# 2_Battery.net
KiCad netlist of a schematic drawn in Altium Designer
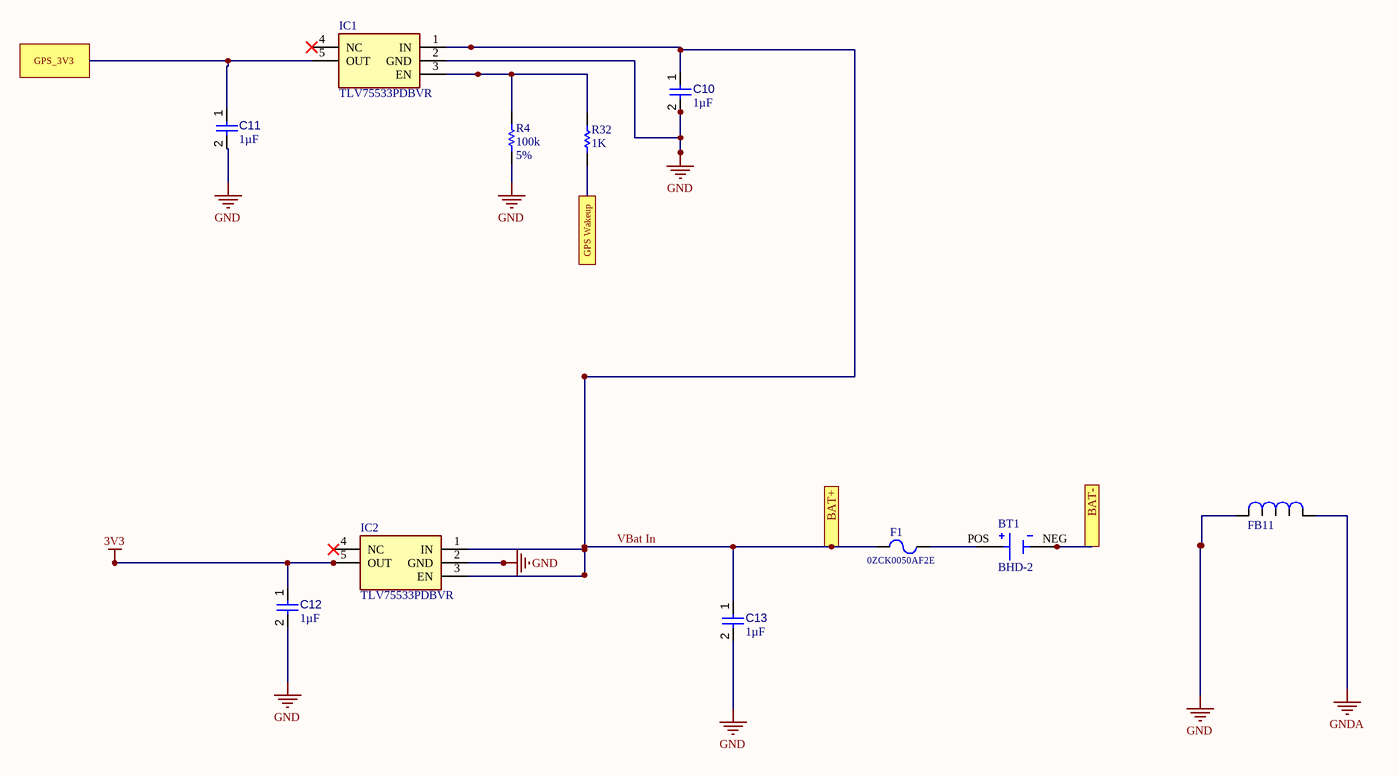
[diagram p0: [2]Battery.SchDoc]

(export (version "E")
  (design (tool "Eeschema 10.0.6"))
  (components
    (comp (ref "BT1")
      (value "BHD-2")
      (footprint "BAT_BHD-2:BAT_BHD-2")
      (description "BATTERY HOLDER D PC PIN")
      (fields
        (field (name "MF") "MPD")
        (field (name "BUYPART") "https://www.snapeda.com/parts/BHD-2/Memory%20Protection%20Devices/view-part/4219639/?ref=eda")
      )
      (libsource (lib "Schlib_For_High_Voltage_Sensor") (part "BHD-2"))
    )
    (comp (ref "C10")
      (value "1µF")
      (footprint "CAPC1608X90X40ML10T20")
      (description "Chip Capacitor, 1 uF, +/- 10%, 25 V, 0603 (1608 Metric)")
      (fields (field (name "TOLERANCE") "10%") (field (name "Comment") "Capacitor 1 uF +/- 10% 25 V 0603"))
      (libsource (lib "Latium Technologies") (part "CAP-NP-2"))
    )
    (comp (ref "C11")
      (value "1µF")
      (footprint "CAPC1608X90X40ML10T20")
      (description "Chip Capacitor, 1 uF, +/- 10%, 25 V, 0603 (1608 Metric)")
      (fields (field (name "TOLERANCE") "10%") (field (name "Comment") "Capacitor 1 uF +/- 10% 25 V 0603"))
      (libsource (lib "Latium Technologies") (part "CAP-NP-2"))
    )
    (comp (ref "C12")
      (value "1µF")
      (footprint "CAPC1608X90X40ML10T20")
      (description "Chip Capacitor, 1 uF, +/- 10%, 25 V, 0603 (1608 Metric)")
      (fields (field (name "TOLERANCE") "10%") (field (name "Comment") "Capacitor 1 uF +/- 10% 25 V 0603"))
      (libsource (lib "Latium Technologies") (part "CAP-NP-2"))
    )
    (comp (ref "C13")
      (value "1µF")
      (footprint "CAPC1608X90X40ML10T20")
      (description "Chip Capacitor, 1 uF, +/- 10%, 25 V, 0603 (1608 Metric)")
      (fields (field (name "TOLERANCE") "10%") (field (name "Comment") "Capacitor 1 uF +/- 10% 25 V 0603"))
      (libsource (lib "Latium Technologies") (part "CAP-NP-2"))
    )
    (comp (ref "F1")
      (value "PTC 9V 500mA")
      (footprint "PcbLibForHigh_Voltage_Sensor:PTC RESET FUSE 9V 500MA 0805")
      (description "PTC RESET FUSE 9V 500MA 0805")
      (fields (field (name "MF PN") "0ZCK0050AF2E"))
      (libsource (lib "MasterLib") (part "PTC RESET FUSE 9V 500MA 0805"))
    )
    (comp (ref "FB11")
      (value "BLM18AG102SN1D")
      (footprint "Ferrite Bead")
      (description "Ferrite Bead 1KOhm @100MHz")
      (libsource (lib "MasterLib") (part "Ferrite Bead"))
    )
    (comp (ref "IC1")
      (value "TLV75533PDBVR")
      (footprint "SamacSys:SOT95P280X145-5N")
      (description "Integrated Circuit")
      (fields (field (name "MOUSER PART NUMBER") "595-TLV75533PDBVR"))
      (libsource (lib "*") (part "TLV75533PDBVR"))
    )
    (comp (ref "IC2")
      (value "TLV75533PDBVR")
      (footprint "SamacSys:SOT95P280X145-5N")
      (description "Integrated Circuit")
      (fields (field (name "MOUSER PART NUMBER") "595-TLV75533PDBVR"))
      (libsource (lib "*") (part "TLV75533PDBVR"))
    )
    (comp (ref "R4")
      (value "100k")
      (footprint "RES 0603")
      (description "RES 100K 5% 0.1W [0603]")
      (fields (field (name "TOLERANCE") "5%"))
      (libsource (lib "MasterLib") (part "RES 3.3M 1% 0.1W [0603]"))
    )
    (comp (ref "R32")
      (value "1K")
      (footprint "RES 0603")
      (description "1K 1% 0.1W [0603]")
      (fields (field (name "TOLERANCE") "1%"))
      (libsource (lib "MasterLib") (part "RES 3.3M 1% 0.1W [0603]"))
    )
  )
  (nets
    (net (code "1") (name "/BAT-") (class "Default")
      (node (ref "BT1") (pin "NEG") (pinfunction "NEG_NEG") (pintype "passive"))
    )
    (net (code "2") (name "/GPS Wakeup") (class "Default")
      (node (ref "R32") (pin "2") (pinfunction "2_2") (pintype "passive"))
    )
    (net (code "3") (name "/GPS_3V3") (class "Default")
      (node (ref "C11") (pin "1") (pinfunction "1_1") (pintype "passive"))
      (node (ref "IC1") (pin "5") (pinfunction "OUT_5") (pintype "passive"))
    )
    (net (code "4") (name "/VBat In") (class "Default")
      (node (ref "C10") (pin "1") (pinfunction "1_1") (pintype "passive"))
      (node (ref "C13") (pin "1") (pinfunction "1_1") (pintype "passive"))
      (node (ref "F1") (pin "1") (pinfunction "1_1") (pintype "passive"))
      (node (ref "IC1") (pin "1") (pinfunction "IN_1") (pintype "passive"))
      (node (ref "IC2") (pin "1") (pinfunction "IN_1") (pintype "passive"))
      (node (ref "IC2") (pin "3") (pinfunction "EN_3") (pintype "passive"))
    )
    (net (code "5") (name "3V3") (class "Default")
      (node (ref "C12") (pin "1") (pinfunction "1_1") (pintype "passive"))
      (node (ref "IC2") (pin "5") (pinfunction "OUT_5") (pintype "passive"))
    )
    (net (code "6") (name "GND") (class "Default")
      (node (ref "C10") (pin "2") (pinfunction "2_2") (pintype "passive"))
      (node (ref "C11") (pin "2") (pinfunction "2_2") (pintype "passive"))
      (node (ref "C12") (pin "2") (pinfunction "2_2") (pintype "passive"))
      (node (ref "C13") (pin "2") (pinfunction "2_2") (pintype "passive"))
      (node (ref "FB11") (pin "2") (pinfunction "2_2") (pintype "passive"))
      (node (ref "IC1") (pin "2") (pinfunction "GND_2") (pintype "passive"))
      (node (ref "IC2") (pin "2") (pinfunction "GND_2") (pintype "passive"))
      (node (ref "R4") (pin "1") (pinfunction "1_1") (pintype "passive"))
    )
    (net (code "7") (name "GNDA") (class "Default")
      (node (ref "FB11") (pin "1") (pinfunction "1_1") (pintype "passive"))
    )
    (net (code "8") (name "Net-(BT1-PadPOS)") (class "Default")
      (node (ref "BT1") (pin "POS") (pinfunction "POS_POS") (pintype "passive"))
      (node (ref "F1") (pin "2") (pinfunction "2_2") (pintype "passive"))
    )
    (net (code "9") (name "Net-(IC1-EN)") (class "Default")
      (node (ref "IC1") (pin "3") (pinfunction "EN_3") (pintype "passive"))
      (node (ref "R32") (pin "1") (pinfunction "1_1") (pintype "passive"))
      (node (ref "R4") (pin "2") (pinfunction "2_2") (pintype "passive"))
    )
    (net (code "10") (name "unconnected-(IC1-NC-Pad4)") (class "Default")
      (node (ref "IC1") (pin "4") (pinfunction "NC_4") (pintype "passive+no_connect"))
    )
    (net (code "11") (name "unconnected-(IC2-NC-Pad4)") (class "Default")
      (node (ref "IC2") (pin "4") (pinfunction "NC_4") (pintype "passive+no_connect"))
    )
  )
)
